# N-FET_Driver.net
KiCad netlist of a schematic drawn in Altium Designer
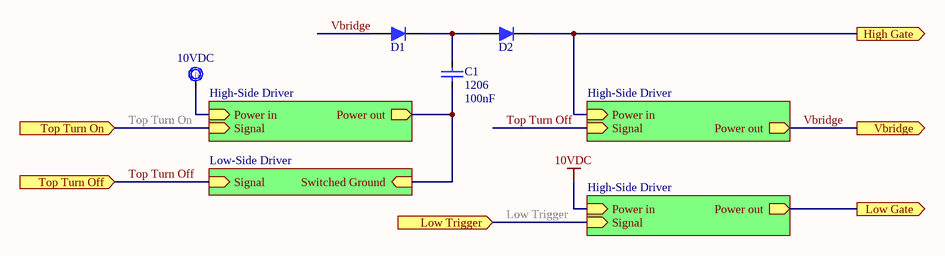
[diagram p0: N-FET Driver.SchDoc]

(export (version "E")
  (design (tool "Eeschema 10.0.6"))
  (components
    (comp (ref "10VDC")
      (value "Test Point")
      (footprint "Test Pad Large")
      (libsource (lib "Integrated Component Library") (part "Test Point"))
    )
    (comp (ref "C1")
      (value "1206")
      (footprint "Capacitor - 1206 Ceramic")
      (description "Non-polarized")
      (fields
        (field (name "MANUFACTURER") "Kemet")
        (field (name "MANUFACTURER PART NUMBER") "C1206C104K5RAC7867")
        (field (name "CAPACITANCE") "100nF")
      )
      (libsource (lib "Integrated Component Library") (part "100nF 1206 50V"))
    )
    (comp (ref "D1")
      (value "Diode - Signal 1A")
      (footprint "SMA - Diode")
      (description "Signal Diode")
      (fields
        (field (name "MANUFACTURER") "Fairchild Semiconductor")
        (field (name "MANUFACTURER PART NUMBER") "RS1M")
      )
      (libsource (lib "Integrated Component Library") (part "Diode - Signal 1A"))
    )
    (comp (ref "D2")
      (value "Diode - Signal 1A")
      (footprint "SMA - Diode")
      (description "Signal Diode")
      (fields
        (field (name "MANUFACTURER") "Fairchild Semiconductor")
        (field (name "MANUFACTURER PART NUMBER") "RS1M")
      )
      (libsource (lib "Integrated Component Library") (part "Diode - Signal 1A"))
    )
  )
  (nets
    (net (code "1") (name "/High Gate") (class "Default")
      (node (ref "D2") (pin "2") (pinfunction "Cathode_2") (pintype "passive"))
    )
    (net (code "4") (name "/Power in") (class "Default")
      (node (ref "10VDC") (pin "1") (pinfunction "1_1") (pintype "passive"))
    )
    (net (code "5") (name "/Power out") (class "Default")
      (node (ref "C1") (pin "2") (pinfunction "2_2") (pintype "passive"))
    )
    (net (code "8") (name "/Vbridge") (class "Default")
      (node (ref "D1") (pin "1") (pinfunction "Anode_1") (pintype "passive"))
    )
    (net (code "10") (name "Net-(D1-Cathode)") (class "Default")
      (node (ref "C1") (pin "1") (pinfunction "1_1") (pintype "passive"))
      (node (ref "D1") (pin "2") (pinfunction "Cathode_2") (pintype "passive"))
      (node (ref "D2") (pin "1") (pinfunction "Anode_1") (pintype "passive"))
    )
  )
)
